# Sheet1.net
KiCad netlist of a schematic drawn in Altium Designer
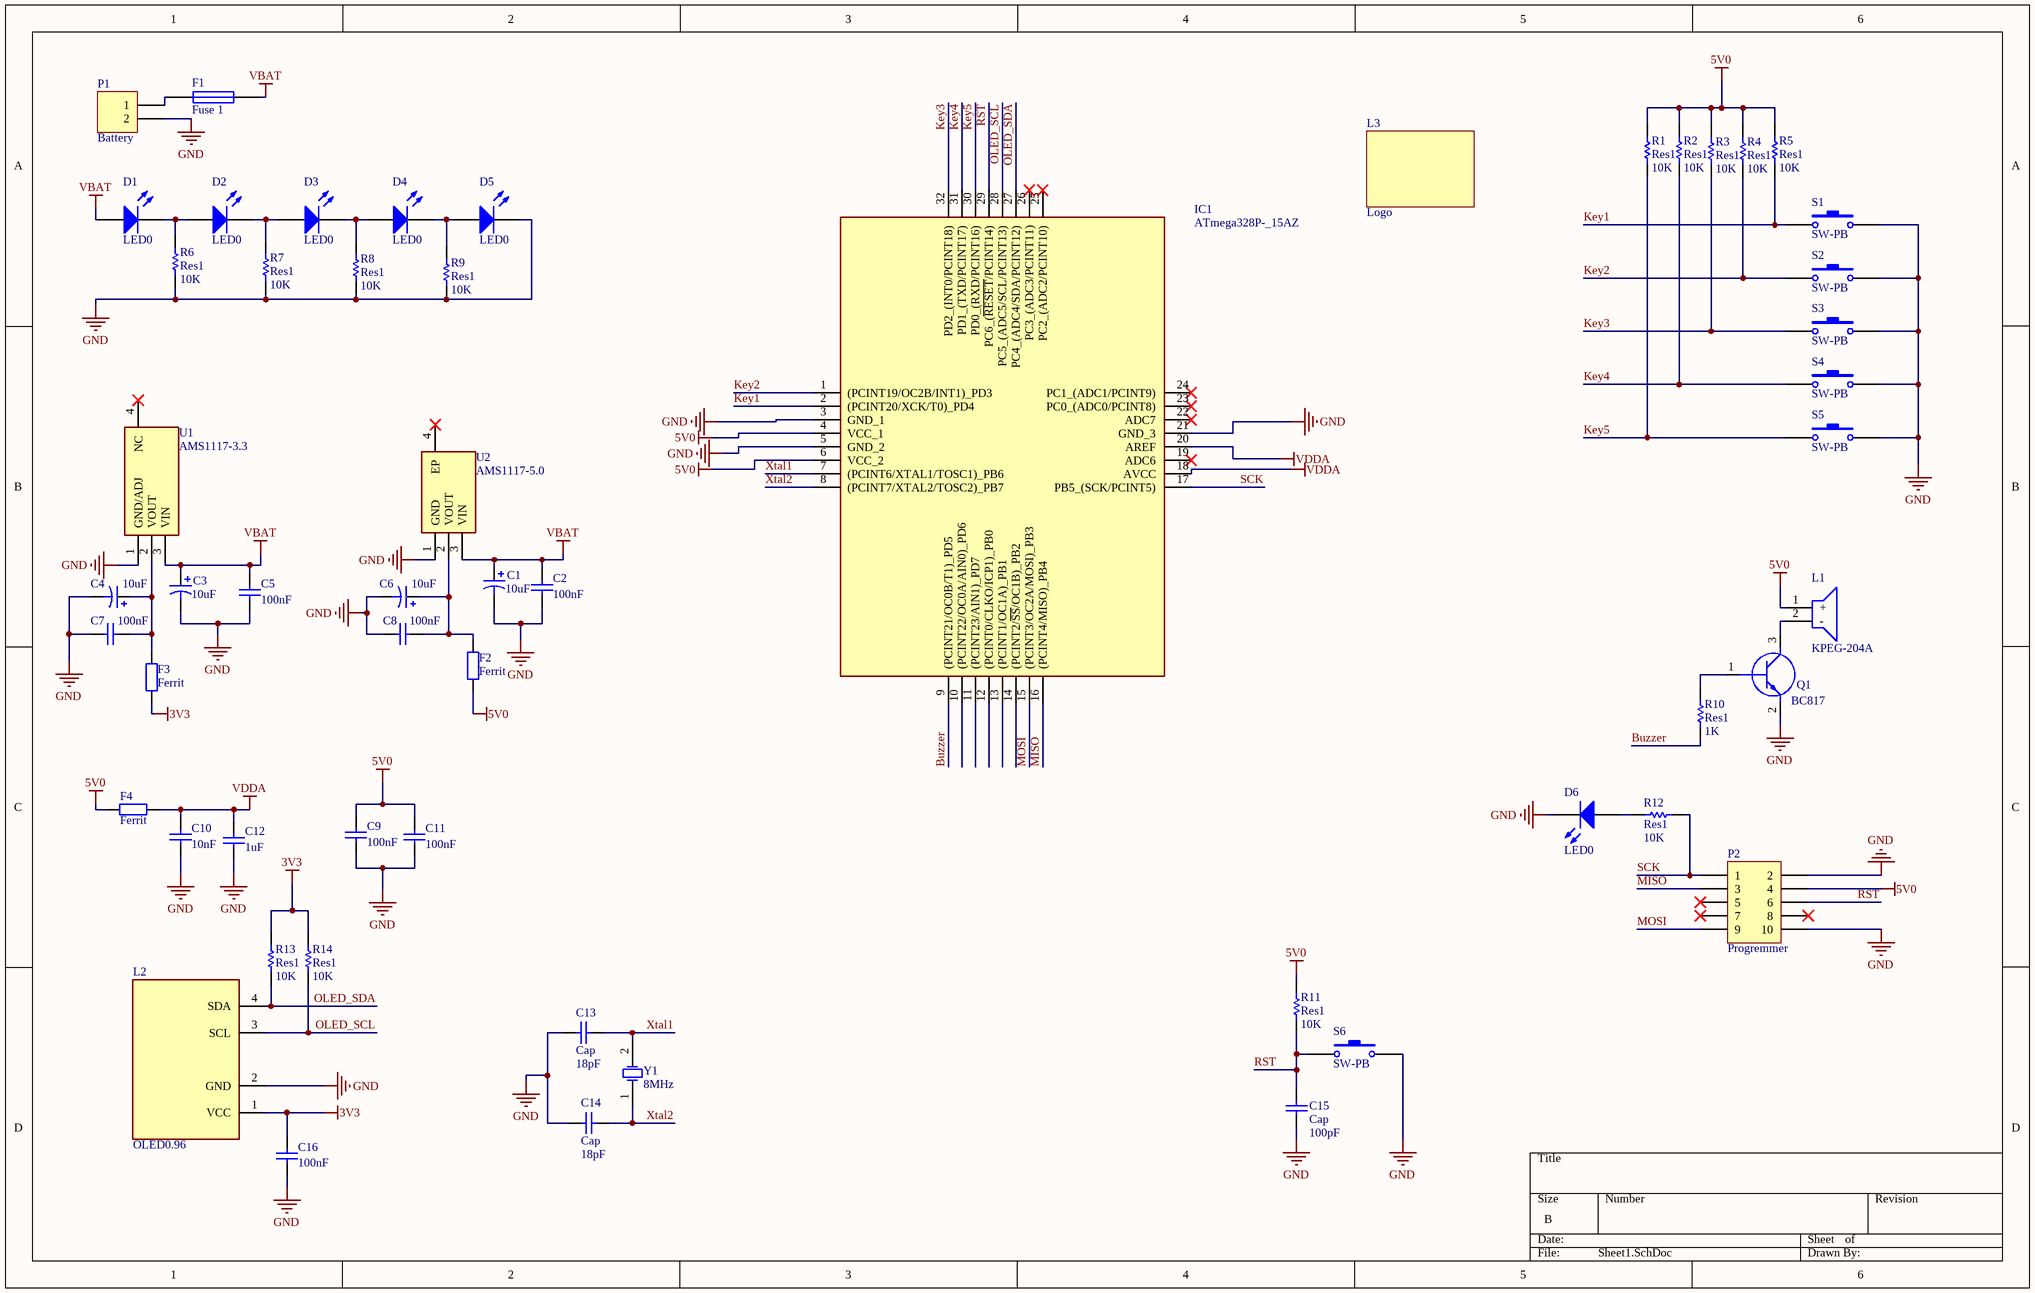
[diagram p0: Sheet1.SchDoc]

(export (version "E")
  (design (tool "Eeschema 10.0.6"))
  (components
    (comp (ref "C1")
      (value "10uF")
      (footprint "Tan-A")
      (description "Polarized Capacitor (Radial)")
      (fields (field (name "Comment") "Cap Pol1") (field (name "PUBLISHER") "Altium Limited"))
      (libsource (lib "Miscellaneous Devices") (part "Cap Pol1"))
    )
    (comp (ref "C2")
      (value "100nF")
      (footprint "603C")
      (description "Capacitor")
      (fields (field (name "Comment") "Cap") (field (name "PUBLISHER") "Altium Limited"))
      (libsource (lib "Miscellaneous Devices") (part "Cap"))
    )
    (comp (ref "C3")
      (value "10uF")
      (footprint "Tan-A")
      (description "Polarized Capacitor (Radial)")
      (fields (field (name "Comment") "Cap Pol1") (field (name "PUBLISHER") "Altium Limited"))
      (libsource (lib "Miscellaneous Devices") (part "Cap Pol1"))
    )
    (comp (ref "C4")
      (value "10uF")
      (footprint "Tan-A")
      (description "Polarized Capacitor (Radial)")
      (fields (field (name "Comment") "Cap Pol1") (field (name "PUBLISHER") "Altium Limited"))
      (libsource (lib "Miscellaneous Devices") (part "Cap Pol1"))
    )
    (comp (ref "C5")
      (value "100nF")
      (footprint "603C")
      (description "Capacitor")
      (fields (field (name "Comment") "Cap") (field (name "PUBLISHER") "Altium Limited"))
      (libsource (lib "Miscellaneous Devices") (part "Cap"))
    )
    (comp (ref "C6")
      (value "10uF")
      (footprint "Tan-A")
      (description "Polarized Capacitor (Radial)")
      (fields (field (name "Comment") "Cap Pol1") (field (name "PUBLISHER") "Altium Limited"))
      (libsource (lib "Miscellaneous Devices") (part "Cap Pol1"))
    )
    (comp (ref "C7")
      (value "100nF")
      (footprint "603C")
      (description "Capacitor")
      (fields (field (name "Comment") "Cap") (field (name "PUBLISHER") "Altium Limited"))
      (libsource (lib "Miscellaneous Devices") (part "Cap"))
    )
    (comp (ref "C8")
      (value "100nF")
      (footprint "603C")
      (description "Capacitor")
      (fields (field (name "Comment") "Cap") (field (name "PUBLISHER") "Altium Limited"))
      (libsource (lib "Miscellaneous Devices") (part "Cap"))
    )
    (comp (ref "C9")
      (value "100nF")
      (footprint "603C")
      (description "Capacitor")
      (fields (field (name "Comment") "Cap") (field (name "PUBLISHER") "Altium Limited"))
      (libsource (lib "Miscellaneous Devices") (part "Cap"))
    )
    (comp (ref "C10")
      (value "10nF")
      (footprint "603C")
      (description "Capacitor")
      (fields (field (name "Comment") "Cap") (field (name "PUBLISHER") "Altium Limited"))
      (libsource (lib "Miscellaneous Devices") (part "Cap"))
    )
    (comp (ref "C11")
      (value "100nF")
      (footprint "603C")
      (description "Capacitor")
      (fields (field (name "Comment") "Cap") (field (name "PUBLISHER") "Altium Limited"))
      (libsource (lib "Miscellaneous Devices") (part "Cap"))
    )
    (comp (ref "C12")
      (value "1uF")
      (footprint "603C")
      (description "Capacitor")
      (fields (field (name "Comment") "Cap") (field (name "PUBLISHER") "Altium Limited"))
      (libsource (lib "Miscellaneous Devices") (part "Cap"))
    )
    (comp (ref "C13")
      (value "Cap")
      (footprint "603C")
      (description "Capacitor")
      (fields (field (name "ALTIUM_VALUE") "18pF") (field (name "PUBLISHER") "Altium Limited"))
      (libsource (lib "Miscellaneous Devices") (part "Cap"))
    )
    (comp (ref "C14")
      (value "Cap")
      (footprint "603C")
      (description "Capacitor")
      (fields (field (name "ALTIUM_VALUE") "18pF") (field (name "PUBLISHER") "Altium Limited"))
      (libsource (lib "Miscellaneous Devices") (part "Cap"))
    )
    (comp (ref "C15")
      (value "Cap")
      (footprint "603C")
      (description "Capacitor")
      (fields (field (name "ALTIUM_VALUE") "100pF") (field (name "PUBLISHER") "Altium Limited"))
      (libsource (lib "Miscellaneous Devices") (part "Cap"))
    )
    (comp (ref "C16")
      (value "100nF")
      (footprint "603C")
      (description "Capacitor")
      (fields (field (name "Comment") "Cap") (field (name "PUBLISHER") "Altium Limited"))
      (libsource (lib "Miscellaneous Devices") (part "Cap"))
    )
    (comp (ref "D1")
      (value "LED0")
      (footprint "LED 0805")
      (description "Typical INFRARED GaAs LED")
      (fields (field (name "PUBLISHER") "Altium Limited"))
      (libsource (lib "Miscellaneous Devices") (part "LED0"))
    )
    (comp (ref "D2")
      (value "LED0")
      (footprint "LED 0805")
      (description "Typical INFRARED GaAs LED")
      (fields (field (name "PUBLISHER") "Altium Limited"))
      (libsource (lib "Miscellaneous Devices") (part "LED0"))
    )
    (comp (ref "D3")
      (value "LED0")
      (footprint "LED 0805")
      (description "Typical INFRARED GaAs LED")
      (fields (field (name "PUBLISHER") "Altium Limited"))
      (libsource (lib "Miscellaneous Devices") (part "LED0"))
    )
    (comp (ref "D4")
      (value "LED0")
      (footprint "LED 0805")
      (description "Typical INFRARED GaAs LED")
      (fields (field (name "PUBLISHER") "Altium Limited"))
      (libsource (lib "Miscellaneous Devices") (part "LED0"))
    )
    (comp (ref "D5")
      (value "LED0")
      (footprint "LED 0805")
      (description "Typical INFRARED GaAs LED")
      (fields (field (name "PUBLISHER") "Altium Limited"))
      (libsource (lib "Miscellaneous Devices") (part "LED0"))
    )
    (comp (ref "D6")
      (value "LED0")
      (footprint "LED 0603")
      (description "Typical INFRARED GaAs LED")
      (fields (field (name "PUBLISHER") "Altium Limited"))
      (libsource (lib "Miscellaneous Devices") (part "LED0"))
    )
    (comp (ref "F1")
      (value "Fuse 1")
      (footprint "Fuse 1206")
      (description "Fuse")
      (fields (field (name "PUBLISHER") "Altium Limited"))
      (libsource (lib "Miscellaneous Devices") (part "Fuse 1"))
    )
    (comp (ref "F2")
      (value "Ferrit")
      (footprint "603FB")
      (description "Resistor")
      (fields (field (name "PUBLISHER") "Altium Limited"))
      (libsource (lib "") (part "Res2_1"))
    )
    (comp (ref "F3")
      (value "Ferrit")
      (footprint "603FB")
      (description "Resistor")
      (fields (field (name "PUBLISHER") "Altium Limited"))
      (libsource (lib "") (part "Res2_1"))
    )
    (comp (ref "F4")
      (value "Ferrit")
      (footprint "603FB")
      (description "Resistor")
      (fields (field (name "PUBLISHER") "Altium Limited"))
      (libsource (lib "Miscellaneous Devices") (part "Res2"))
    )
    (comp (ref "IC1")
      (value "ATmega328P-_15AZ")
      (footprint "ATMEGA328P-15AZ")
      (description "AVR AVR® ATmega Microcontroller IC 8-Bit 16MHz 32KB (16K x 16) FLASH 32-TQFP (7x7)")
      (fields (field (name "MANUFACTURER_PART_NUMBER") "ATmega328P- 15AZ"))
      (libsource (lib "AbbasSchLib") (part "ATmega328P_15AZ"))
    )
    (comp (ref "L1")
      (value "KPEG-204A")
      (footprint "KPEG204A")
      (libsource (lib "AbbasSchLib") (part "KPEG-204A"))
    )
    (comp (ref "L2")
      (value "OLED0.96")
      (footprint "OLED0.96")
      (description "OLED 0.96 I2C")
      (libsource (lib "AbbasSchLib") (part "OLED0.96"))
    )
    (comp (ref "L3")
      (value "Logo")
      (footprint "Logo Abbas Lashgari")
      (description "Abbas Lashgari Logo")
      (libsource (lib "AbbasSchLib") (part "Logo"))
    )
    (comp (ref "P1")
      (value "Battery")
      (footprint "XH-B2B")
      (description "Header, 2-Pin")
      (fields (field (name "PUBLISHER") "Altium Limited"))
      (libsource (lib "Miscellaneous Connectors") (part "Header 2"))
    )
    (comp (ref "P2")
      (value "Progremmer")
      (footprint "IDC-2*5")
      (description "Header, 5-Pin, Dual row")
      (fields (field (name "PUBLISHER") "Altium Limited"))
      (libsource (lib "Miscellaneous Connectors") (part "Header 5X2"))
    )
    (comp (ref "Q1")
      (value "BC817")
      (footprint "BC817")
      (description "45 V, 500 mA NPN general-purpose transistors")
      (libsource (lib "AbbasSchLib") (part "BC817"))
    )
    (comp (ref "R1")
      (value "Res1")
      (footprint "603R")
      (description "Resistor")
      (fields (field (name "ALTIUM_VALUE") "10K") (field (name "PUBLISHER") "Altium Limited"))
      (libsource (lib "Miscellaneous Devices") (part "Res1"))
    )
    (comp (ref "R2")
      (value "Res1")
      (footprint "603R")
      (description "Resistor")
      (fields (field (name "ALTIUM_VALUE") "10K") (field (name "PUBLISHER") "Altium Limited"))
      (libsource (lib "Miscellaneous Devices") (part "Res1"))
    )
    (comp (ref "R3")
      (value "Res1")
      (footprint "603R")
      (description "Resistor")
      (fields (field (name "ALTIUM_VALUE") "10K") (field (name "PUBLISHER") "Altium Limited"))
      (libsource (lib "Miscellaneous Devices") (part "Res1"))
    )
    (comp (ref "R4")
      (value "Res1")
      (footprint "603R")
      (description "Resistor")
      (fields (field (name "ALTIUM_VALUE") "10K") (field (name "PUBLISHER") "Altium Limited"))
      (libsource (lib "Miscellaneous Devices") (part "Res1"))
    )
    (comp (ref "R5")
      (value "Res1")
      (footprint "603R")
      (description "Resistor")
      (fields (field (name "ALTIUM_VALUE") "10K") (field (name "PUBLISHER") "Altium Limited"))
      (libsource (lib "Miscellaneous Devices") (part "Res1"))
    )
    (comp (ref "R6")
      (value "Res1")
      (footprint "603R")
      (description "Resistor")
      (fields (field (name "ALTIUM_VALUE") "10K") (field (name "PUBLISHER") "Altium Limited"))
      (libsource (lib "Miscellaneous Devices") (part "Res1"))
    )
    (comp (ref "R7")
      (value "Res1")
      (footprint "603R")
      (description "Resistor")
      (fields (field (name "ALTIUM_VALUE") "10K") (field (name "PUBLISHER") "Altium Limited"))
      (libsource (lib "Miscellaneous Devices") (part "Res1"))
    )
    (comp (ref "R8")
      (value "Res1")
      (footprint "603R")
      (description "Resistor")
      (fields (field (name "ALTIUM_VALUE") "10K") (field (name "PUBLISHER") "Altium Limited"))
      (libsource (lib "Miscellaneous Devices") (part "Res1"))
    )
    (comp (ref "R9")
      (value "Res1")
      (footprint "603R")
      (description "Resistor")
      (fields (field (name "ALTIUM_VALUE") "10K") (field (name "PUBLISHER") "Altium Limited"))
      (libsource (lib "Miscellaneous Devices") (part "Res1"))
    )
    (comp (ref "R10")
      (value "Res1")
      (footprint "603R")
      (description "Resistor")
      (fields (field (name "ALTIUM_VALUE") "1K") (field (name "PUBLISHER") "Altium Limited"))
      (libsource (lib "Miscellaneous Devices") (part "Res1"))
    )
    (comp (ref "R11")
      (value "Res1")
      (footprint "603R")
      (description "Resistor")
      (fields (field (name "ALTIUM_VALUE") "10K") (field (name "PUBLISHER") "Altium Limited"))
      (libsource (lib "Miscellaneous Devices") (part "Res1"))
    )
    (comp (ref "R12")
      (value "Res1")
      (footprint "603R")
      (description "Resistor")
      (fields (field (name "ALTIUM_VALUE") "10K") (field (name "PUBLISHER") "Altium Limited"))
      (libsource (lib "Miscellaneous Devices") (part "Res1"))
    )
    (comp (ref "R13")
      (value "Res1")
      (footprint "603R")
      (description "Resistor")
      (fields (field (name "ALTIUM_VALUE") "10K") (field (name "PUBLISHER") "Altium Limited"))
      (libsource (lib "Miscellaneous Devices") (part "Res1"))
    )
    (comp (ref "R14")
      (value "Res1")
      (footprint "603R")
      (description "Resistor")
      (fields (field (name "ALTIUM_VALUE") "10K") (field (name "PUBLISHER") "Altium Limited"))
      (libsource (lib "Miscellaneous Devices") (part "Res1"))
    )
    (comp (ref "S1")
      (value "SW-PB")
      (footprint "SW_2pin")
      (description "Switch")
      (fields (field (name "PUBLISHER") "Altium Limited"))
      (libsource (lib "Miscellaneous Devices") (part "SW-PB"))
    )
    (comp (ref "S2")
      (value "SW-PB")
      (footprint "SW_2pin")
      (description "Switch")
      (fields (field (name "PUBLISHER") "Altium Limited"))
      (libsource (lib "Miscellaneous Devices") (part "SW-PB"))
    )
    (comp (ref "S3")
      (value "SW-PB")
      (footprint "SW_2pin")
      (description "Switch")
      (fields (field (name "PUBLISHER") "Altium Limited"))
      (libsource (lib "Miscellaneous Devices") (part "SW-PB"))
    )
    (comp (ref "S4")
      (value "SW-PB")
      (footprint "SW_2pin")
      (description "Switch")
      (fields (field (name "PUBLISHER") "Altium Limited"))
      (libsource (lib "Miscellaneous Devices") (part "SW-PB"))
    )
    (comp (ref "S5")
      (value "SW-PB")
      (footprint "SW_2pin")
      (description "Switch")
      (fields (field (name "PUBLISHER") "Altium Limited"))
      (libsource (lib "Miscellaneous Devices") (part "SW-PB"))
    )
    (comp (ref "S6")
      (value "SW-PB")
      (footprint "SW_2pin")
      (description "Switch")
      (fields (field (name "PUBLISHER") "Altium Limited"))
      (libsource (lib "Miscellaneous Devices") (part "SW-PB"))
    )
    (comp (ref "U1")
      (value "AMS1117-3.3")
      (footprint "AMS1117-3.3")
      (description "LDO Voltage Regulators 3.3V")
      (libsource (lib "AbbasSchLib") (part "AMS1117-3.3"))
    )
    (comp (ref "U2")
      (value "AMS1117-5.0")
      (footprint "AMS1117-5.0")
      (description "LDO Voltage Regulators 5.0V")
      (libsource (lib "AbbasSchLib") (part "AMS1117-5.0"))
    )
    (comp (ref "Y1")
      (value "8MHz")
      (footprint "ABM3")
      (description "Crystal Oscillator")
      (fields (field (name "PUBLISHER") "Altium Limited"))
      (libsource (lib "Miscellaneous Devices") (part "XTAL"))
    )
  )
  (nets
    (net (code "1") (name "/Buzzer") (class "Default")
      (node (ref "IC1") (pin "9") (pinfunction "(PCINT21/OC0B/T1)_PD5_9") (pintype "passive"))
      (node (ref "R10") (pin "2") (pinfunction "2_2") (pintype "passive"))
    )
    (net (code "2") (name "/Key1") (class "Default")
      (node (ref "IC1") (pin "2") (pinfunction "(PCINT20/XCK/T0)_PD4_2") (pintype "passive"))
      (node (ref "R5") (pin "1") (pinfunction "1_1") (pintype "passive"))
      (node (ref "S1") (pin "1") (pinfunction "1_1") (pintype "passive"))
    )
    (net (code "3") (name "/Key2") (class "Default")
      (node (ref "IC1") (pin "1") (pinfunction "(PCINT19/OC2B/INT1)_PD3_1") (pintype "passive"))
      (node (ref "R4") (pin "1") (pinfunction "1_1") (pintype "passive"))
      (node (ref "S2") (pin "1") (pinfunction "1_1") (pintype "passive"))
    )
    (net (code "4") (name "/Key3") (class "Default")
      (node (ref "IC1") (pin "32") (pinfunction "PD2_(INT0/PCINT18)_32") (pintype "passive"))
      (node (ref "R3") (pin "1") (pinfunction "1_1") (pintype "passive"))
      (node (ref "S3") (pin "1") (pinfunction "1_1") (pintype "passive"))
    )
    (net (code "5") (name "/Key4") (class "Default")
      (node (ref "IC1") (pin "31") (pinfunction "PD1_(TXD/PCINT17)_31") (pintype "passive"))
      (node (ref "R2") (pin "1") (pinfunction "1_1") (pintype "passive"))
      (node (ref "S4") (pin "1") (pinfunction "1_1") (pintype "passive"))
    )
    (net (code "6") (name "/Key5") (class "Default")
      (node (ref "IC1") (pin "30") (pinfunction "PD0_(RXD/PCINT16)_30") (pintype "passive"))
      (node (ref "R1") (pin "1") (pinfunction "1_1") (pintype "passive"))
      (node (ref "S5") (pin "1") (pinfunction "1_1") (pintype "passive"))
    )
    (net (code "7") (name "/MISO") (class "Default")
      (node (ref "IC1") (pin "16") (pinfunction "(PCINT4/MISO)_PB4_16") (pintype "passive"))
      (node (ref "P2") (pin "3") (pinfunction "3_3") (pintype "passive"))
    )
    (net (code "8") (name "/MOSI") (class "Default")
      (node (ref "IC1") (pin "15") (pinfunction "(PCINT3/OC2A/MOSI)_PB3_15") (pintype "passive"))
      (node (ref "P2") (pin "9") (pinfunction "9_9") (pintype "passive"))
    )
    (net (code "9") (name "/OLED_SCL") (class "Default")
      (node (ref "IC1") (pin "28") (pinfunction "PC5_(ADC5/SCL/PCINT13)_28") (pintype "passive"))
      (node (ref "L2") (pin "3") (pinfunction "SCL_3") (pintype "passive"))
      (node (ref "R14") (pin "1") (pinfunction "1_1") (pintype "passive"))
    )
    (net (code "10") (name "/OLED_SDA") (class "Default")
      (node (ref "IC1") (pin "27") (pinfunction "PC4_(ADC4/SDA/PCINT12)_27") (pintype "passive"))
      (node (ref "L2") (pin "4") (pinfunction "SDA_4") (pintype "passive"))
      (node (ref "R13") (pin "1") (pinfunction "1_1") (pintype "passive"))
    )
    (net (code "11") (name "/RST") (class "Default")
      (node (ref "C15") (pin "2") (pinfunction "2_2") (pintype "passive"))
      (node (ref "IC1") (pin "29") (pinfunction "PC6_(~{RESET}/PCINT14)_29") (pintype "passive"))
      (node (ref "P2") (pin "6") (pinfunction "6_6") (pintype "passive"))
      (node (ref "R11") (pin "1") (pinfunction "1_1") (pintype "passive"))
      (node (ref "S6") (pin "1") (pinfunction "1_1") (pintype "passive"))
    )
    (net (code "12") (name "/SCK") (class "Default")
      (node (ref "IC1") (pin "17") (pinfunction "PB5_(SCK/PCINT5)_17") (pintype "passive"))
      (node (ref "P2") (pin "1") (pinfunction "1_1") (pintype "passive"))
      (node (ref "R12") (pin "1") (pinfunction "1_1") (pintype "passive"))
    )
    (net (code "13") (name "/Xtal1") (class "Default")
      (node (ref "C13") (pin "2") (pinfunction "2_2") (pintype "passive"))
      (node (ref "IC1") (pin "7") (pinfunction "(PCINT6/XTAL1/TOSC1)_PB6_7") (pintype "passive"))
      (node (ref "Y1") (pin "2") (pinfunction "OSC2_2") (pintype "passive"))
    )
    (net (code "14") (name "/Xtal2") (class "Default")
      (node (ref "C14") (pin "2") (pinfunction "2_2") (pintype "passive"))
      (node (ref "IC1") (pin "8") (pinfunction "(PCINT7/XTAL2/TOSC2)_PB7_8") (pintype "passive"))
      (node (ref "Y1") (pin "1") (pinfunction "OSC1_1") (pintype "passive"))
    )
    (net (code "15") (name "3V3") (class "Default")
      (node (ref "C16") (pin "2") (pinfunction "2_2") (pintype "passive"))
      (node (ref "F3") (pin "1") (pinfunction "1_1") (pintype "passive"))
      (node (ref "L2") (pin "1") (pinfunction "VCC_1") (pintype "passive"))
      (node (ref "R13") (pin "2") (pinfunction "2_2") (pintype "passive"))
      (node (ref "R14") (pin "2") (pinfunction "2_2") (pintype "passive"))
    )
    (net (code "16") (name "5V0") (class "Default")
      (node (ref "C11") (pin "2") (pinfunction "2_2") (pintype "passive"))
      (node (ref "C9") (pin "2") (pinfunction "2_2") (pintype "passive"))
      (node (ref "F2") (pin "1") (pinfunction "1_1") (pintype "passive"))
      (node (ref "F4") (pin "2") (pinfunction "2_2") (pintype "passive"))
      (node (ref "IC1") (pin "4") (pinfunction "VCC_1_4") (pintype "passive"))
      (node (ref "IC1") (pin "6") (pinfunction "VCC_2_6") (pintype "passive"))
      (node (ref "L1") (pin "1") (pinfunction "+_1") (pintype "passive"))
      (node (ref "P2") (pin "4") (pinfunction "4_4") (pintype "passive"))
      (node (ref "R1") (pin "2") (pinfunction "2_2") (pintype "passive"))
      (node (ref "R11") (pin "2") (pinfunction "2_2") (pintype "passive"))
      (node (ref "R2") (pin "2") (pinfunction "2_2") (pintype "passive"))
      (node (ref "R3") (pin "2") (pinfunction "2_2") (pintype "passive"))
      (node (ref "R4") (pin "2") (pinfunction "2_2") (pintype "passive"))
      (node (ref "R5") (pin "2") (pinfunction "2_2") (pintype "passive"))
    )
    (net (code "17") (name "GND") (class "Default")
      (node (ref "C1") (pin "2") (pinfunction "2_2") (pintype "passive"))
      (node (ref "C10") (pin "1") (pinfunction "1_1") (pintype "passive"))
      (node (ref "C11") (pin "1") (pinfunction "1_1") (pintype "passive"))
      (node (ref "C12") (pin "1") (pinfunction "1_1") (pintype "passive"))
      (node (ref "C13") (pin "1") (pinfunction "1_1") (pintype "passive"))
      (node (ref "C14") (pin "1") (pinfunction "1_1") (pintype "passive"))
      (node (ref "C15") (pin "1") (pinfunction "1_1") (pintype "passive"))
      (node (ref "C16") (pin "1") (pinfunction "1_1") (pintype "passive"))
      (node (ref "C2") (pin "1") (pinfunction "1_1") (pintype "passive"))
      (node (ref "C3") (pin "2") (pinfunction "2_2") (pintype "passive"))
      (node (ref "C4") (pin "2") (pinfunction "2_2") (pintype "passive"))
      (node (ref "C5") (pin "1") (pinfunction "1_1") (pintype "passive"))
      (node (ref "C6") (pin "2") (pinfunction "2_2") (pintype "passive"))
      (node (ref "C7") (pin "2") (pinfunction "2_2") (pintype "passive"))
      (node (ref "C8") (pin "2") (pinfunction "2_2") (pintype "passive"))
      (node (ref "C9") (pin "1") (pinfunction "1_1") (pintype "passive"))
      (node (ref "D5") (pin "2") (pinfunction "K_2") (pintype "passive"))
      (node (ref "D6") (pin "2") (pinfunction "K_2") (pintype "passive"))
      (node (ref "IC1") (pin "21") (pinfunction "GND_3_21") (pintype "passive"))
      (node (ref "IC1") (pin "3") (pinfunction "GND_1_3") (pintype "passive"))
      (node (ref "IC1") (pin "5") (pinfunction "GND_2_5") (pintype "passive"))
      (node (ref "L2") (pin "2") (pinfunction "GND_2") (pintype "passive"))
      (node (ref "P1") (pin "2") (pinfunction "2_2") (pintype "passive"))
      (node (ref "P2") (pin "10") (pinfunction "10_10") (pintype "passive"))
      (node (ref "P2") (pin "2") (pinfunction "2_2") (pintype "passive"))
      (node (ref "Q1") (pin "2") (pinfunction "E_2") (pintype "passive"))
      (node (ref "R6") (pin "1") (pinfunction "1_1") (pintype "passive"))
      (node (ref "R7") (pin "1") (pinfunction "1_1") (pintype "passive"))
      (node (ref "R8") (pin "1") (pinfunction "1_1") (pintype "passive"))
      (node (ref "R9") (pin "1") (pinfunction "1_1") (pintype "passive"))
      (node (ref "S1") (pin "2") (pinfunction "2_2") (pintype "passive"))
      (node (ref "S2") (pin "2") (pinfunction "2_2") (pintype "passive"))
      (node (ref "S3") (pin "2") (pinfunction "2_2") (pintype "passive"))
      (node (ref "S4") (pin "2") (pinfunction "2_2") (pintype "passive"))
      (node (ref "S5") (pin "2") (pinfunction "2_2") (pintype "passive"))
      (node (ref "S6") (pin "2") (pinfunction "2_2") (pintype "passive"))
      (node (ref "U1") (pin "1") (pinfunction "GND/ADJ_1") (pintype "passive"))
      (node (ref "U2") (pin "1") (pinfunction "GND_1") (pintype "passive"))
    )
    (net (code "18") (name "Net-(D1-K)") (class "Default")
      (node (ref "D1") (pin "2") (pinfunction "K_2") (pintype "passive"))
      (node (ref "D2") (pin "1") (pinfunction "A_1") (pintype "passive"))
      (node (ref "R6") (pin "2") (pinfunction "2_2") (pintype "passive"))
    )
    (net (code "19") (name "Net-(D2-K)") (class "Default")
      (node (ref "D2") (pin "2") (pinfunction "K_2") (pintype "passive"))
      (node (ref "D3") (pin "1") (pinfunction "A_1") (pintype "passive"))
      (node (ref "R7") (pin "2") (pinfunction "2_2") (pintype "passive"))
    )
    (net (code "20") (name "Net-(D3-K)") (class "Default")
      (node (ref "D3") (pin "2") (pinfunction "K_2") (pintype "passive"))
      (node (ref "D4") (pin "1") (pinfunction "A_1") (pintype "passive"))
      (node (ref "R8") (pin "2") (pinfunction "2_2") (pintype "passive"))
    )
    (net (code "21") (name "Net-(D4-K)") (class "Default")
      (node (ref "D4") (pin "2") (pinfunction "K_2") (pintype "passive"))
      (node (ref "D5") (pin "1") (pinfunction "A_1") (pintype "passive"))
      (node (ref "R9") (pin "2") (pinfunction "2_2") (pintype "passive"))
    )
    (net (code "22") (name "Net-(D6-A)") (class "Default")
      (node (ref "D6") (pin "1") (pinfunction "A_1") (pintype "passive"))
      (node (ref "R12") (pin "2") (pinfunction "2_2") (pintype "passive"))
    )
    (net (code "23") (name "Net-(F1-Pad1)") (class "Default")
      (node (ref "F1") (pin "1") (pinfunction "1_1") (pintype "passive"))
      (node (ref "P1") (pin "1") (pinfunction "1_1") (pintype "passive"))
    )
    (net (code "24") (name "Net-(L1--)") (class "Default")
      (node (ref "L1") (pin "2") (pinfunction "-_2") (pintype "passive"))
      (node (ref "Q1") (pin "3") (pinfunction "C_3") (pintype "passive"))
    )
    (net (code "25") (name "Net-(Q1-B)") (class "Default")
      (node (ref "Q1") (pin "1") (pinfunction "B_1") (pintype "passive"))
      (node (ref "R10") (pin "1") (pinfunction "1_1") (pintype "passive"))
    )
    (net (code "26") (name "Net-(U1-VOUT)") (class "Default")
      (node (ref "C4") (pin "1") (pinfunction "1_1") (pintype "passive"))
      (node (ref "C7") (pin "1") (pinfunction "1_1") (pintype "passive"))
      (node (ref "F3") (pin "2") (pinfunction "2_2") (pintype "passive"))
      (node (ref "U1") (pin "2") (pinfunction "VOUT_2") (pintype "passive"))
    )
    (net (code "27") (name "Net-(U2-VOUT)") (class "Default")
      (node (ref "C6") (pin "1") (pinfunction "1_1") (pintype "passive"))
      (node (ref "C8") (pin "1") (pinfunction "1_1") (pintype "passive"))
      (node (ref "F2") (pin "2") (pinfunction "2_2") (pintype "passive"))
      (node (ref "U2") (pin "2") (pinfunction "VOUT_2") (pintype "passive"))
    )
    (net (code "28") (name "VBAT") (class "Default")
      (node (ref "C1") (pin "1") (pinfunction "1_1") (pintype "passive"))
      (node (ref "C2") (pin "2") (pinfunction "2_2") (pintype "passive"))
      (node (ref "C3") (pin "1") (pinfunction "1_1") (pintype "passive"))
      (node (ref "C5") (pin "2") (pinfunction "2_2") (pintype "passive"))
      (node (ref "D1") (pin "1") (pinfunction "A_1") (pintype "passive"))
      (node (ref "F1") (pin "2") (pinfunction "2_2") (pintype "passive"))
      (node (ref "U1") (pin "3") (pinfunction "VIN_3") (pintype "passive"))
      (node (ref "U2") (pin "3") (pinfunction "VIN_3") (pintype "passive"))
    )
    (net (code "29") (name "VDDA") (class "Default")
      (node (ref "C10") (pin "2") (pinfunction "2_2") (pintype "passive"))
      (node (ref "C12") (pin "2") (pinfunction "2_2") (pintype "passive"))
      (node (ref "F4") (pin "1") (pinfunction "1_1") (pintype "passive"))
      (node (ref "IC1") (pin "18") (pinfunction "AVCC_18") (pintype "passive"))
      (node (ref "IC1") (pin "20") (pinfunction "AREF_20") (pintype "passive"))
    )
    (net (code "30") (name "unconnected-(IC1-(PCINT0{slash}CLKO{slash}ICP1)_PB0-Pad12)") (class "Default")
      (node (ref "IC1") (pin "12") (pinfunction "(PCINT0/CLKO/ICP1)_PB0_12") (pintype "passive"))
    )
    (net (code "31") (name "unconnected-(IC1-(PCINT1{slash}OC1A)_PB1-Pad13)") (class "Default")
      (node (ref "IC1") (pin "13") (pinfunction "(PCINT1/OC1A)_PB1_13") (pintype "passive"))
    )
    (net (code "32") (name "unconnected-(IC1-(PCINT2{slash}~{SS}{slash}OC1B)_PB2-Pad14)") (class "Default")
      (node (ref "IC1") (pin "14") (pinfunction "(PCINT2/~{SS}/OC1B)_PB2_14") (pintype "passive"))
    )
    (net (code "33") (name "unconnected-(IC1-(PCINT22{slash}OC0A{slash}AIN0)_PD6-Pad10)") (class "Default")
      (node (ref "IC1") (pin "10") (pinfunction "(PCINT22/OC0A/AIN0)_PD6_10") (pintype "passive"))
    )
    (net (code "34") (name "unconnected-(IC1-(PCINT23{slash}AIN1)_PD7-Pad11)") (class "Default")
      (node (ref "IC1") (pin "11") (pinfunction "(PCINT23/AIN1)_PD7_11") (pintype "passive"))
    )
    (net (code "35") (name "unconnected-(IC1-ADC6-Pad19)") (class "Default")
      (node (ref "IC1") (pin "19") (pinfunction "ADC6_19") (pintype "passive+no_connect"))
    )
    (net (code "36") (name "unconnected-(IC1-ADC7-Pad22)") (class "Default")
      (node (ref "IC1") (pin "22") (pinfunction "ADC7_22") (pintype "passive+no_connect"))
    )
    (net (code "37") (name "unconnected-(IC1-PC0_(ADC0{slash}PCINT8)-Pad23)") (class "Default")
      (node (ref "IC1") (pin "23") (pinfunction "PC0_(ADC0/PCINT8)_23") (pintype "passive+no_connect"))
    )
    (net (code "38") (name "unconnected-(IC1-PC1_(ADC1{slash}PCINT9)-Pad24)") (class "Default")
      (node (ref "IC1") (pin "24") (pinfunction "PC1_(ADC1/PCINT9)_24") (pintype "passive+no_connect"))
    )
    (net (code "39") (name "unconnected-(IC1-PC2_(ADC2{slash}PCINT10)-Pad25)") (class "Default")
      (node (ref "IC1") (pin "25") (pinfunction "PC2_(ADC2/PCINT10)_25") (pintype "passive+no_connect"))
    )
    (net (code "40") (name "unconnected-(IC1-PC3_(ADC3{slash}PCINT11)-Pad26)") (class "Default")
      (node (ref "IC1") (pin "26") (pinfunction "PC3_(ADC3/PCINT11)_26") (pintype "passive+no_connect"))
    )
    (net (code "41") (name "unconnected-(P2-Pad5)") (class "Default")
      (node (ref "P2") (pin "5") (pinfunction "5_5") (pintype "passive+no_connect"))
    )
    (net (code "42") (name "unconnected-(P2-Pad7)") (class "Default")
      (node (ref "P2") (pin "7") (pinfunction "7_7") (pintype "passive+no_connect"))
    )
    (net (code "43") (name "unconnected-(P2-Pad8)") (class "Default")
      (node (ref "P2") (pin "8") (pinfunction "8_8") (pintype "passive+no_connect"))
    )
    (net (code "44") (name "unconnected-(U1-NC-Pad4)") (class "Default")
      (node (ref "U1") (pin "4") (pinfunction "NC_4") (pintype "passive+no_connect"))
    )
    (net (code "45") (name "unconnected-(U2-EP-Pad4)") (class "Default")
      (node (ref "U2") (pin "4") (pinfunction "EP_4") (pintype "passive+no_connect"))
    )
  )
)
